# RFModule.net
KiCad netlist of a schematic drawn in Altium Designer
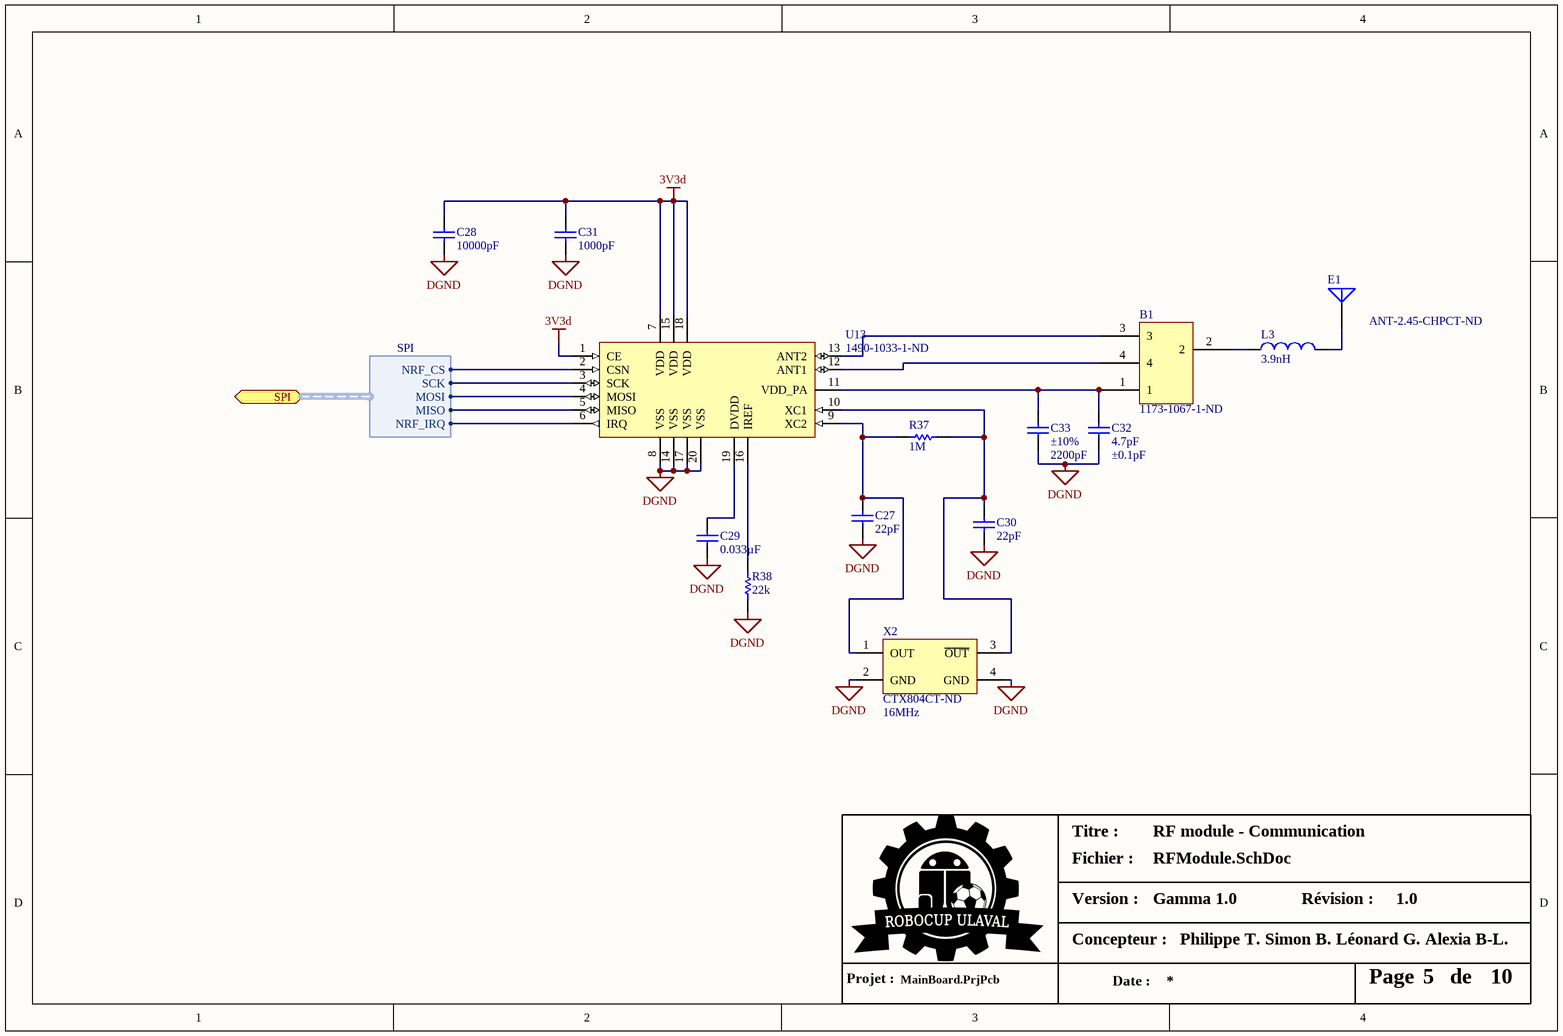
[diagram p0: RFModule.SchDoc]

(export (version "E")
  (design (tool "Eeschema 10.0.6"))
  (components
    (comp (ref "B1")
      (value "BD2425NNRF")
      (footprint "BD2425NNRF")
      (description "XFRMR BALUN RF 2400-2500MHZ 0404")
      (fields (field (name "MANUFACTURER") "Anaren") (field (name "SUPPLIER PART NUMBER 1") "1173-1067-1-ND"))
      (libsource (lib "MainBoard") (part "BD2425NNRF"))
    )
    (comp (ref "C27")
      (value "CL10C220GB8NNNC")
      (footprint "0603")
      (description "CAP CER 22PF 50V NP0 0603")
      (fields
        (field (name "MANUFACTURER") "Samsung Electro-Mechanics America, Inc.")
        (field (name "TOLERANCE") "±2%")
        (field (name "CAPACITANCE") "22pF")
      )
      (libsource (lib "ResCap") (part "CL10C220GB8NNNC"))
    )
    (comp (ref "C28")
      (value "GRM188R71H103KA01D")
      (footprint "0603")
      (description "CAP CER 10000PF 50V X7R 0603")
      (fields
        (field (name "MANUFACTURER") "Murata Electronics North America")
        (field (name "TOLERANCE") "±10%")
        (field (name "CAPACITANCE") "10000pF")
      )
      (libsource (lib "ResCap") (part "GRM188R71H103KA01D"))
    )
    (comp (ref "C29")
      (value "CL10B333KB8SFNC")
      (footprint "0603")
      (description "CAP CER 0.033UF 50V X7R 0603")
      (fields
        (field (name "MANUFACTURER") "Samsung Electro-Mechanics America, Inc.")
        (field (name "TOLERANCE") "±10%")
        (field (name "CAPACITANCE") "0.033µF")
      )
      (libsource (lib "ResCap") (part "CL10B333KB8SFNC"))
    )
    (comp (ref "C30")
      (value "CL10C220GB8NNNC")
      (footprint "0603")
      (description "CAP CER 22PF 50V NP0 0603")
      (fields
        (field (name "MANUFACTURER") "Samsung Electro-Mechanics America, Inc.")
        (field (name "TOLERANCE") "±2%")
        (field (name "CAPACITANCE") "22pF")
      )
      (libsource (lib "ResCap") (part "CL10C220GB8NNNC"))
    )
    (comp (ref "C31")
      (value "CL10B102KB8NNNC")
      (footprint "0603")
      (description "CAP CER 1000PF 50V X7R 0603")
      (fields
        (field (name "MANUFACTURER") "Samsung Electro-Mechanics America, Inc.")
        (field (name "TOLERANCE") "±10%")
        (field (name "CAPACITANCE") "1000pF")
      )
      (libsource (lib "ResCap") (part "CL10B102KB8NNNC"))
    )
    (comp (ref "C32")
      (value "GRM1555C1E4R7BA01D")
      (footprint "0402")
      (description "CAP CER 4.7PF 25V NP0 0402")
      (fields
        (field (name "MANUFACTURER") "Murata Electronics North America")
        (field (name "CAPACITANCE") "4.7pF")
        (field (name "TOLERANCE") "±0.1pF")
      )
      (libsource (lib "MainBoard") (part "GRM1555C1E4R7BA01D"))
    )
    (comp (ref "C33")
      (value "GRM155R61A222KA01D")
      (footprint "0402")
      (description "CAP CER 2200PF 10V X5R 0402")
      (fields
        (field (name "MANUFACTURER") "Murata Electronics North America")
        (field (name "TOLERANCE") "±10%")
        (field (name "CAPACITANCE") "2200pF")
      )
      (libsource (lib "MainBoard") (part "GRM155R61A222KA01D"))
    )
    (comp (ref "E1")
      (value "ANT-2.45-CHP-T")
      (footprint "ANT-2.45-CHP-x")
      (description "ANT 2.4GHZ 802.11 BLUETOOTH SMD")
      (fields
        (field (name "MANUFACTURER") "Linx Technologies Inc.")
        (field (name "SUPPLIER PART NUMBER 1") "ANT-2.45-CHPCT-ND")
      )
      (libsource (lib "MainBoard") (part "ANT-2.45-CHP-T"))
    )
    (comp (ref "L3")
      (value "LQP15MN3N9B02D")
      (footprint "0402")
      (description "FIXED IND 3.9NH 170MA 500 MOHM")
      (fields
        (field (name "MANUFACTURER") "Murata Electronics North America")
        (field (name "TOLERANCE") "±0.1nH")
        (field (name "INDUCTANCE") "3.9nH")
      )
      (libsource (lib "MainBoard") (part "LQP15MN3N9B02D"))
    )
    (comp (ref "R37")
      (value "RC0603FR-071ML")
      (footprint "0603")
      (description "RES SMD 1M OHM 1% 1/10W 0603")
      (fields
        (field (name "MANUFACTURER") "Yageo")
        (field (name "TOLERANCE") "±1%")
        (field (name "RESISTANCE (OHMS)") "1M")
      )
      (libsource (lib "ResCap") (part "RC0603FR-071ML"))
    )
    (comp (ref "R38")
      (value "RC0603FR-0722KL")
      (footprint "0603")
      (description "RES SMD 22K OHM 1% 1/10W 0603")
      (fields
        (field (name "MANUFACTURER") "Yageo")
        (field (name "TOLERANCE") "±1%")
        (field (name "RESISTANCE (OHMS)") "22k")
      )
      (libsource (lib "ResCap") (part "RC0603FR-0722KL"))
    )
    (comp (ref "U13")
      (value "NRF24L01P-R7")
      (footprint "QFN40P300X300X80_HS-21N")
      (description "IC RF TXRX ISM>1GHZ 20-VFQFN")
      (fields
        (field (name "MANUFACTURER") "Nordic Semiconductor ASA")
        (field (name "SUPPLIER PART NUMBER 1") "1490-1033-1-ND")
      )
      (libsource (lib "MainBoard") (part "NRF24L01P-R7"))
    )
    (comp (ref "X2")
      (value "425F35B016M0000")
      (footprint "QFN138P200X250X65-4N")
      (description "CRYSTAL 16.0000MHZ 13PF SMD")
      (fields
        (field (name "MANUFACTURER") "CTS-Frequency Controls")
        (field (name "SUPPLIER PART NUMBER 1") "CTX804CT-ND")
        (field (name "FREQUENCY") "16MHz")
      )
      (libsource (lib "MainBoard") (part "425F35B016M0000"))
    )
  )
  (nets
    (net (code "2") (name "/MISO") (class "Default")
      (node (ref "U13") (pin "5") (pinfunction "MISO_5") (pintype "bidirectional"))
    )
    (net (code "3") (name "/MOSI") (class "Default")
      (node (ref "U13") (pin "4") (pinfunction "MOSI_4") (pintype "bidirectional"))
    )
    (net (code "4") (name "/NRF_CS") (class "Default")
      (node (ref "U13") (pin "2") (pinfunction "CSN_2") (pintype "input"))
    )
    (net (code "5") (name "/NRF_IRQ") (class "Default")
      (node (ref "U13") (pin "6") (pinfunction "IRQ_6") (pintype "output"))
    )
    (net (code "6") (name "/SCK") (class "Default")
      (node (ref "U13") (pin "3") (pinfunction "SCK_3") (pintype "bidirectional"))
    )
    (net (code "8") (name "3V3d") (class "Default")
      (node (ref "C28") (pin "2") (pinfunction "2_2") (pintype "passive"))
      (node (ref "C31") (pin "2") (pinfunction "2_2") (pintype "passive"))
      (node (ref "U13") (pin "1") (pinfunction "CE_1") (pintype "input"))
      (node (ref "U13") (pin "15") (pinfunction "VDD_15") (pintype "power_in"))
      (node (ref "U13") (pin "18") (pinfunction "VDD_18") (pintype "power_in"))
      (node (ref "U13") (pin "7") (pinfunction "VDD_7") (pintype "power_in"))
    )
    (net (code "9") (name "DGND") (class "Default")
      (node (ref "C27") (pin "1") (pinfunction "1_1") (pintype "passive"))
      (node (ref "C28") (pin "1") (pinfunction "1_1") (pintype "passive"))
      (node (ref "C29") (pin "1") (pinfunction "1_1") (pintype "passive"))
      (node (ref "C30") (pin "1") (pinfunction "1_1") (pintype "passive"))
      (node (ref "C31") (pin "1") (pinfunction "1_1") (pintype "passive"))
      (node (ref "C32") (pin "1") (pinfunction "1_1") (pintype "passive"))
      (node (ref "C33") (pin "1") (pinfunction "1_1") (pintype "passive"))
      (node (ref "R38") (pin "1") (pinfunction "1_1") (pintype "passive"))
      (node (ref "U13") (pin "14") (pinfunction "VSS_14") (pintype "power_in"))
      (node (ref "U13") (pin "17") (pinfunction "VSS_17") (pintype "power_in"))
      (node (ref "U13") (pin "20") (pinfunction "VSS_20") (pintype "power_in"))
      (node (ref "U13") (pin "8") (pinfunction "VSS_8") (pintype "power_in"))
      (node (ref "X2") (pin "2") (pinfunction "GND_2") (pintype "power_in"))
      (node (ref "X2") (pin "4") (pinfunction "GND_4") (pintype "power_in"))
    )
    (net (code "10") (name "Net-(B1-Pad2)") (class "Default")
      (node (ref "B1") (pin "2") (pinfunction "2_2") (pintype "passive"))
      (node (ref "L3") (pin "1") (pinfunction "1_1") (pintype "passive"))
    )
    (net (code "11") (name "Net-(E1-A)") (class "Default")
      (node (ref "E1") (pin "1") (pinfunction "A_1") (pintype "passive"))
      (node (ref "L3") (pin "2") (pinfunction "2_2") (pintype "passive"))
    )
    (net (code "12") (name "Net-(U13-ANT1)") (class "Default")
      (node (ref "B1") (pin "4") (pinfunction "4_4") (pintype "passive"))
      (node (ref "U13") (pin "12") (pinfunction "ANT1_12") (pintype "bidirectional"))
    )
    (net (code "13") (name "Net-(U13-ANT2)") (class "Default")
      (node (ref "B1") (pin "3") (pinfunction "3_3") (pintype "passive"))
      (node (ref "U13") (pin "13") (pinfunction "ANT2_13") (pintype "bidirectional"))
    )
    (net (code "14") (name "Net-(U13-DVDD)") (class "Default")
      (node (ref "C29") (pin "2") (pinfunction "2_2") (pintype "passive"))
      (node (ref "U13") (pin "19") (pinfunction "DVDD_19") (pintype "passive"))
    )
    (net (code "15") (name "Net-(U13-IREF)") (class "Default")
      (node (ref "R38") (pin "2") (pinfunction "2_2") (pintype "passive"))
      (node (ref "U13") (pin "16") (pinfunction "IREF_16") (pintype "passive"))
    )
    (net (code "16") (name "Net-(U13-VDD_PA)") (class "Default")
      (node (ref "B1") (pin "1") (pinfunction "1_1") (pintype "passive"))
      (node (ref "C32") (pin "2") (pinfunction "2_2") (pintype "passive"))
      (node (ref "C33") (pin "2") (pinfunction "2_2") (pintype "passive"))
      (node (ref "U13") (pin "11") (pinfunction "VDD_PA_11") (pintype "passive"))
    )
    (net (code "17") (name "Net-(U13-XC1)") (class "Default")
      (node (ref "C30") (pin "2") (pinfunction "2_2") (pintype "passive"))
      (node (ref "R37") (pin "2") (pinfunction "2_2") (pintype "passive"))
      (node (ref "U13") (pin "10") (pinfunction "XC1_10") (pintype "input"))
      (node (ref "X2") (pin "3") (pinfunction "~{OUT}_3") (pintype "power_in"))
    )
    (net (code "18") (name "Net-(U13-XC2)") (class "Default")
      (node (ref "C27") (pin "2") (pinfunction "2_2") (pintype "passive"))
      (node (ref "R37") (pin "1") (pinfunction "1_1") (pintype "passive"))
      (node (ref "U13") (pin "9") (pinfunction "XC2_9") (pintype "input"))
      (node (ref "X2") (pin "1") (pinfunction "OUT_1") (pintype "power_in"))
    )
  )
)
